# MCU.net
KiCad netlist of a schematic drawn in EAGLE
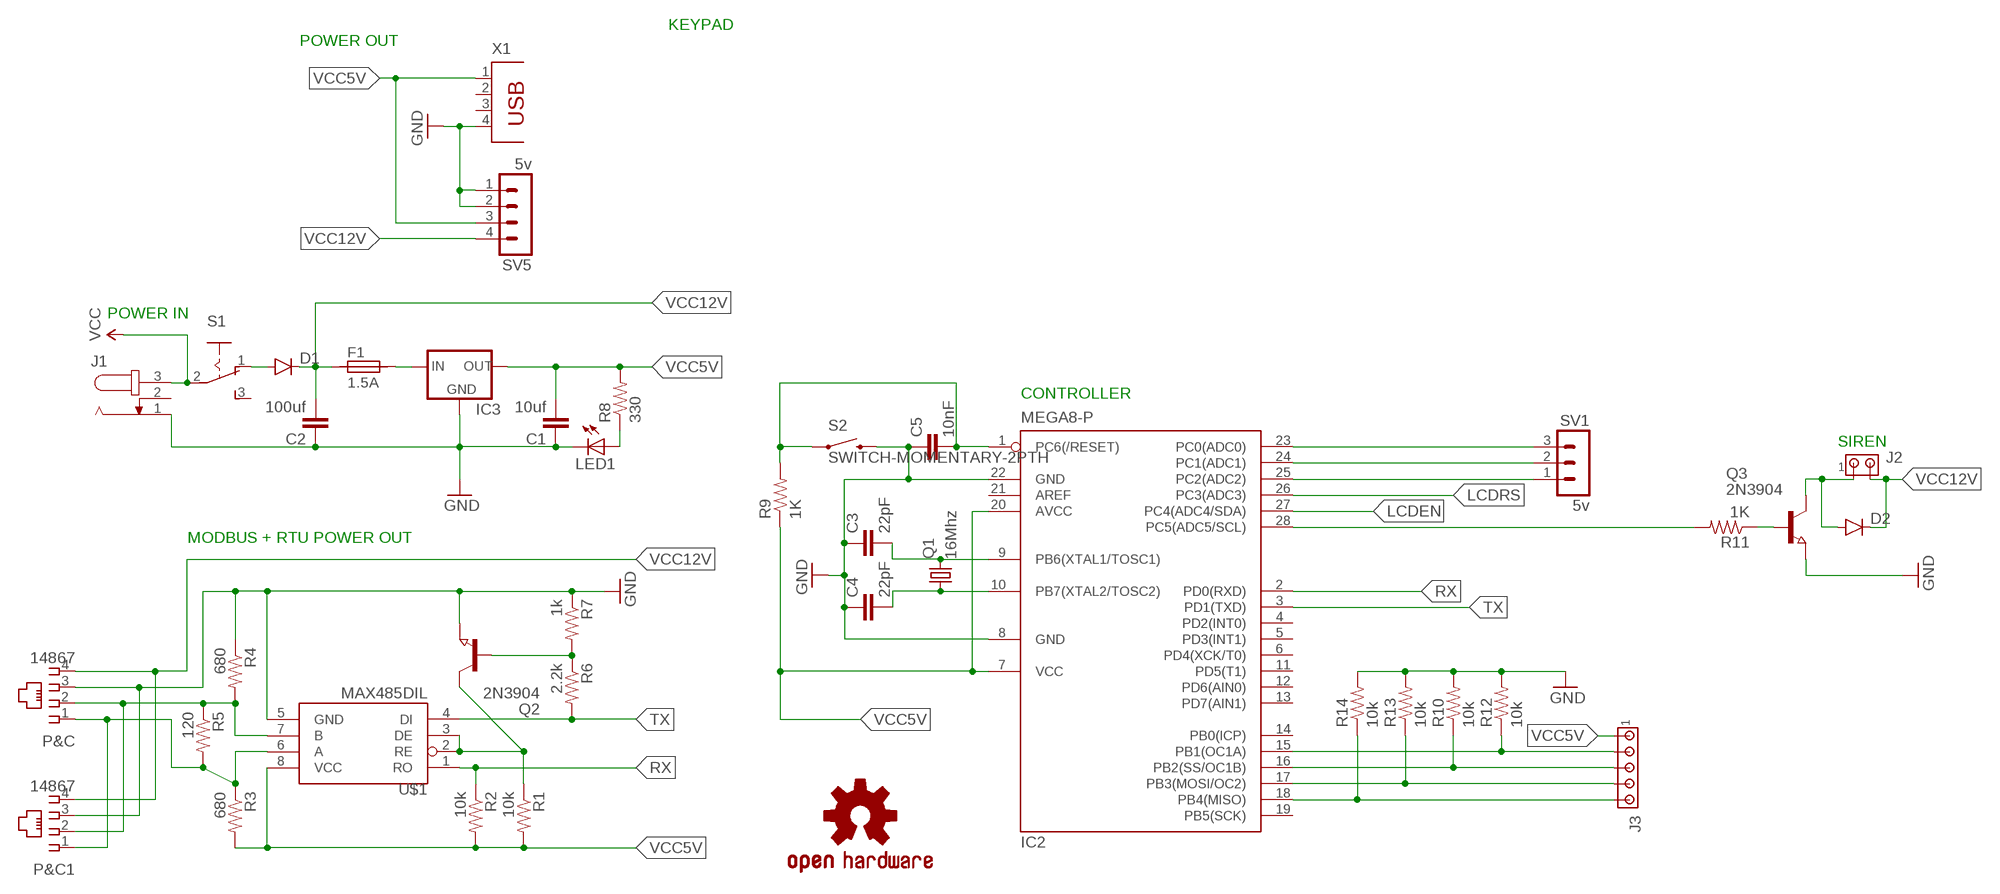
[diagram p0: schematic, sheet 1]

(export (version "E")
  (design (tool "Eeschema 10.0.6"))
  (components
    (comp (ref "C1")
      (value "10uf")
      (footprint "eagle-import:0805")
      (libsource (lib "eagle-import") (part "CAP0805"))
    )
    (comp (ref "C2")
      (value "100uf")
      (footprint "eagle-import:0805")
      (libsource (lib "eagle-import") (part "CAP0805"))
    )
    (comp (ref "C3")
      (value "22pF")
      (footprint "eagle-import:0805")
      (libsource (lib "eagle-import") (part "CAP0805"))
    )
    (comp (ref "C4")
      (value "22pF")
      (footprint "eagle-import:0805")
      (libsource (lib "eagle-import") (part "CAP0805"))
    )
    (comp (ref "C5")
      (value "10nF")
      (footprint "eagle-import:0805")
      (libsource (lib "eagle-import") (part "CAP0805"))
    )
    (comp (ref "D1")
      (value "DIODESMA")
      (footprint "eagle-import:SMA-DIODE")
      (libsource (lib "eagle-import") (part "DIODESMA"))
    )
    (comp (ref "D2")
      (value "DIODESMA")
      (footprint "eagle-import:SMA-DIODE")
      (libsource (lib "eagle-import") (part "DIODESMA"))
    )
    (comp (ref "F1")
      (value "1.5A")
      (footprint "eagle-import:1820")
      (libsource (lib "eagle-import") (part "SIBA194600"))
    )
    (comp (ref "IC2")
      (value "MEGA8-P")
      (footprint "eagle-import:DIL28-3")
      (libsource (lib "eagle-import") (part "MEGA8-P"))
    )
    (comp (ref "IC3")
      (value "V_REG_78XX-TO-220")
      (footprint "eagle-import:TO-220-ALT")
      (libsource (lib "eagle-import") (part "V_REG_78XX-TO-220"))
    )
    (comp (ref "J1")
      (value "JACK-PLUG1")
      (footprint "eagle-import:SPC4078")
      (libsource (lib "eagle-import") (part "JACK-PLUG1"))
    )
    (comp (ref "J2")
      (value "MTA02-156")
      (footprint "eagle-import:1X2MTA")
      (libsource (lib "eagle-import") (part "MTA02-156"))
    )
    (comp (ref "J3")
      (value "MTA05-156")
      (footprint "eagle-import:1X5MTA")
      (libsource (lib "eagle-import") (part "MTA05-156"))
    )
    (comp (ref "LED1")
      (value "LEDCHIP-LED0805")
      (footprint "eagle-import:CHIP-LED0805")
      (libsource (lib "eagle-import") (part "LEDCHIP-LED0805"))
    )
    (comp (ref "LOGO1")
      (value "OSHW-LOGOL")
      (footprint "eagle-import:OSHW-LOGO-L")
      (libsource (lib "eagle-import") (part "OSHW-LOGOL"))
    )
    (comp (ref "P&C")
      (value "14867")
      (footprint "eagle-import:14867")
      (libsource (lib "eagle-import") (part "14867"))
    )
    (comp (ref "P&C1")
      (value "14867")
      (footprint "eagle-import:14867")
      (libsource (lib "eagle-import") (part "14867"))
    )
    (comp (ref "Q1")
      (value "16Mhz")
      (footprint "eagle-import:SM49")
      (libsource (lib "eagle-import") (part "CRYSTALSM49"))
    )
    (comp (ref "Q2")
      (value "2N3904")
      (footprint "eagle-import:SOT23")
      (libsource (lib "eagle-import") (part "NPN-TRANSISTOR_SOT23"))
    )
    (comp (ref "Q3")
      (value "2N3904")
      (footprint "eagle-import:SOT23")
      (libsource (lib "eagle-import") (part "NPN-TRANSISTOR_SOT23"))
    )
    (comp (ref "R1")
      (value "10k")
      (footprint "eagle-import:0805")
      (libsource (lib "eagle-import") (part "RESISTOR0805-RES"))
    )
    (comp (ref "R2")
      (value "10k")
      (footprint "eagle-import:0805")
      (libsource (lib "eagle-import") (part "RESISTOR0805-RES"))
    )
    (comp (ref "R3")
      (value "680")
      (footprint "eagle-import:0805")
      (libsource (lib "eagle-import") (part "RESISTOR0805-RES"))
    )
    (comp (ref "R4")
      (value "680")
      (footprint "eagle-import:0805")
      (libsource (lib "eagle-import") (part "RESISTOR0805-RES"))
    )
    (comp (ref "R5")
      (value "120")
      (footprint "eagle-import:0805")
      (libsource (lib "eagle-import") (part "RESISTOR0805-RES"))
    )
    (comp (ref "R6")
      (value "2.2k")
      (footprint "eagle-import:0805")
      (libsource (lib "eagle-import") (part "RESISTOR0805-RES"))
    )
    (comp (ref "R7")
      (value "1k")
      (footprint "eagle-import:0805")
      (libsource (lib "eagle-import") (part "RESISTOR0805-RES"))
    )
    (comp (ref "R8")
      (value "330")
      (footprint "eagle-import:0805")
      (libsource (lib "eagle-import") (part "RESISTOR0805-RES"))
    )
    (comp (ref "R9")
      (value "1K")
      (footprint "eagle-import:0805")
      (libsource (lib "eagle-import") (part "RESISTOR0805-RES"))
    )
    (comp (ref "R10")
      (value "10k")
      (footprint "eagle-import:0805")
      (libsource (lib "eagle-import") (part "RESISTOR0805-RES"))
    )
    (comp (ref "R11")
      (value "1K")
      (footprint "eagle-import:0805")
      (libsource (lib "eagle-import") (part "RESISTOR0805-RES"))
    )
    (comp (ref "R12")
      (value "10k")
      (footprint "eagle-import:0805")
      (libsource (lib "eagle-import") (part "RESISTOR0805-RES"))
    )
    (comp (ref "R13")
      (value "10k")
      (footprint "eagle-import:0805")
      (libsource (lib "eagle-import") (part "RESISTOR0805-RES"))
    )
    (comp (ref "R14")
      (value "10k")
      (footprint "eagle-import:0805")
      (libsource (lib "eagle-import") (part "RESISTOR0805-RES"))
    )
    (comp (ref "S1")
      (value "255SB")
      (footprint "eagle-import:255SB")
      (libsource (lib "eagle-import") (part "255SB"))
    )
    (comp (ref "S2")
      (value "SWITCH-MOMENTARY-2PTH")
      (footprint "eagle-import:TACTILE-PTH")
      (libsource (lib "eagle-import") (part "SWITCH-MOMENTARY-2PTH"))
    )
    (comp (ref "SV1")
      (value "5v")
      (footprint "eagle-import:MA03-1")
      (libsource (lib "eagle-import") (part "MA03-1"))
    )
    (comp (ref "SV5")
      (value "5v")
      (footprint "eagle-import:MA04-1")
      (libsource (lib "eagle-import") (part "MA04-1"))
    )
    (comp (ref "U$1")
      (value "MAX485DIL")
      (footprint "eagle-import:DIL08")
      (libsource (lib "eagle-import") (part "MAX485DIL"))
    )
    (comp (ref "X1")
      (value "PN87520")
      (footprint "eagle-import:PN87520")
      (libsource (lib "eagle-import") (part "PN87520"))
    )
  )
  (nets
    (net (code "1") (name "GND") (class "Default")
      (node (ref "C1") (pin "1") (pinfunction "1_1") (pintype "passive"))
      (node (ref "C2") (pin "1") (pinfunction "1_1") (pintype "passive"))
      (node (ref "C3") (pin "1") (pinfunction "1_1") (pintype "passive"))
      (node (ref "C4") (pin "1") (pinfunction "1_1") (pintype "passive"))
      (node (ref "C5") (pin "1") (pinfunction "1_1") (pintype "passive"))
      (node (ref "IC2") (pin "22") (pinfunction "GND_22") (pintype "power_in"))
      (node (ref "IC2") (pin "8") (pinfunction "GND_8") (pintype "power_in"))
      (node (ref "IC3") (pin "GND") (pinfunction "GND_GND") (pintype "input"))
      (node (ref "J1") (pin "1") (pinfunction "1_1") (pintype "passive"))
      (node (ref "LED1") (pin "C") (pinfunction "C_C") (pintype "passive"))
      (node (ref "P&C") (pin "3") (pinfunction "3_3") (pintype "passive"))
      (node (ref "P&C1") (pin "3") (pinfunction "3_3") (pintype "passive"))
      (node (ref "Q2") (pin "2") (pinfunction "E_2") (pintype "passive"))
      (node (ref "Q3") (pin "2") (pinfunction "E_2") (pintype "passive"))
      (node (ref "R10") (pin "2") (pinfunction "2_2") (pintype "passive"))
      (node (ref "R12") (pin "2") (pinfunction "2_2") (pintype "passive"))
      (node (ref "R13") (pin "2") (pinfunction "2_2") (pintype "passive"))
      (node (ref "R14") (pin "2") (pinfunction "2_2") (pintype "passive"))
      (node (ref "R4") (pin "1") (pinfunction "1_1") (pintype "passive"))
      (node (ref "R7") (pin "1") (pinfunction "1_1") (pintype "passive"))
      (node (ref "S2") (pin "3") (pinfunction "2_3") (pintype "passive"))
      (node (ref "SV5") (pin "1") (pinfunction "1_1") (pintype "passive"))
      (node (ref "SV5") (pin "2") (pinfunction "2_2") (pintype "passive"))
      (node (ref "U$1") (pin "5") (pinfunction "GND_5") (pintype "bidirectional"))
      (node (ref "X1") (pin "4") (pinfunction "4_4") (pintype "passive"))
    )
    (net (code "2") (name "LCDEN") (class "Default")
      (node (ref "IC2") (pin "27") (pinfunction "PC4(ADC4/SDA)_27") (pintype "bidirectional"))
    )
    (net (code "3") (name "LCDRS") (class "Default")
      (node (ref "IC2") (pin "26") (pinfunction "PC3(ADC3)_26") (pintype "bidirectional"))
    )
    (net (code "4") (name "Net-(F1-Pad2)") (class "Default")
      (node (ref "F1") (pin "2") (pinfunction "2_2") (pintype "passive"))
      (node (ref "IC3") (pin "IN") (pinfunction "IN_IN") (pintype "input"))
    )
    (net (code "5") (name "Net-(IC2-PB1(OC1A))") (class "Default")
      (node (ref "IC2") (pin "15") (pinfunction "PB1(OC1A)_15") (pintype "bidirectional"))
      (node (ref "J3") (pin "2") (pinfunction "2_2") (pintype "passive"))
      (node (ref "R12") (pin "1") (pinfunction "1_1") (pintype "passive"))
    )
    (net (code "6") (name "Net-(IC2-PB2(SS{slash}OC1B))") (class "Default")
      (node (ref "IC2") (pin "16") (pinfunction "PB2(SS/OC1B)_16") (pintype "bidirectional"))
      (node (ref "J3") (pin "3") (pinfunction "3_3") (pintype "passive"))
      (node (ref "R10") (pin "1") (pinfunction "1_1") (pintype "passive"))
    )
    (net (code "7") (name "Net-(IC2-PB3(MOSI{slash}OC2))") (class "Default")
      (node (ref "IC2") (pin "17") (pinfunction "PB3(MOSI/OC2)_17") (pintype "bidirectional"))
      (node (ref "J3") (pin "4") (pinfunction "4_4") (pintype "passive"))
      (node (ref "R13") (pin "1") (pinfunction "1_1") (pintype "passive"))
    )
    (net (code "8") (name "Net-(IC2-PB4(MISO))") (class "Default")
      (node (ref "IC2") (pin "18") (pinfunction "PB4(MISO)_18") (pintype "bidirectional"))
      (node (ref "J3") (pin "5") (pinfunction "5_5") (pintype "passive"))
      (node (ref "R14") (pin "1") (pinfunction "1_1") (pintype "passive"))
    )
    (net (code "9") (name "Net-(IC2-PB6(XTAL1{slash}TOSC1))") (class "Default")
      (node (ref "C3") (pin "2") (pinfunction "2_2") (pintype "passive"))
      (node (ref "IC2") (pin "9") (pinfunction "PB6(XTAL1/TOSC1)_9") (pintype "bidirectional"))
      (node (ref "Q1") (pin "2") (pinfunction "2_2") (pintype "passive"))
    )
    (net (code "10") (name "Net-(IC2-PB7(XTAL2{slash}TOSC2))") (class "Default")
      (node (ref "C4") (pin "2") (pinfunction "2_2") (pintype "passive"))
      (node (ref "IC2") (pin "10") (pinfunction "PB7(XTAL2/TOSC2)_10") (pintype "bidirectional"))
      (node (ref "Q1") (pin "1") (pinfunction "1_1") (pintype "passive"))
    )
    (net (code "11") (name "Net-(IC2-PC0(ADC0))") (class "Default")
      (node (ref "IC2") (pin "23") (pinfunction "PC0(ADC0)_23") (pintype "bidirectional"))
      (node (ref "SV1") (pin "3") (pinfunction "3_3") (pintype "passive"))
    )
    (net (code "12") (name "Net-(IC2-PC1(ADC1))") (class "Default")
      (node (ref "IC2") (pin "24") (pinfunction "PC1(ADC1)_24") (pintype "bidirectional"))
      (node (ref "SV1") (pin "2") (pinfunction "2_2") (pintype "passive"))
    )
    (net (code "13") (name "Net-(IC2-PC2(ADC2))") (class "Default")
      (node (ref "IC2") (pin "25") (pinfunction "PC2(ADC2)_25") (pintype "bidirectional"))
      (node (ref "SV1") (pin "1") (pinfunction "1_1") (pintype "passive"))
    )
    (net (code "14") (name "Net-(IC2-PC5(ADC5{slash}SCL))") (class "Default")
      (node (ref "IC2") (pin "28") (pinfunction "PC5(ADC5/SCL)_28") (pintype "bidirectional"))
      (node (ref "R11") (pin "2") (pinfunction "2_2") (pintype "passive"))
    )
    (net (code "15") (name "Net-(IC2-PC6({slash}RESET))") (class "Default")
      (node (ref "C5") (pin "2") (pinfunction "2_2") (pintype "passive"))
      (node (ref "IC2") (pin "1") (pinfunction "PC6(/RESET)_1") (pintype "bidirectional"))
      (node (ref "R9") (pin "2") (pinfunction "2_2") (pintype "passive"))
      (node (ref "S2") (pin "1") (pinfunction "1_1") (pintype "passive"))
    )
    (net (code "16") (name "Net-(LED1-PadA)") (class "Default")
      (node (ref "LED1") (pin "A") (pinfunction "A_A") (pintype "passive"))
      (node (ref "R8") (pin "1") (pinfunction "1_1") (pintype "passive"))
    )
    (net (code "17") (name "Net-(Q2-B)") (class "Default")
      (node (ref "Q2") (pin "1") (pinfunction "B_1") (pintype "passive"))
      (node (ref "R6") (pin "1") (pinfunction "1_1") (pintype "passive"))
      (node (ref "R7") (pin "2") (pinfunction "2_2") (pintype "passive"))
    )
    (net (code "18") (name "Net-(Q2-C)") (class "Default")
      (node (ref "Q2") (pin "3") (pinfunction "C_3") (pintype "passive"))
      (node (ref "R1") (pin "1") (pinfunction "1_1") (pintype "passive"))
      (node (ref "U$1") (pin "2") (pinfunction "RE_2") (pintype "bidirectional"))
      (node (ref "U$1") (pin "3") (pinfunction "DE_3") (pintype "bidirectional"))
    )
    (net (code "19") (name "Net-(Q3-B)") (class "Default")
      (node (ref "Q3") (pin "1") (pinfunction "B_1") (pintype "passive"))
      (node (ref "R11") (pin "1") (pinfunction "1_1") (pintype "passive"))
    )
    (net (code "20") (name "Net-(Q3-C)") (class "Default")
      (node (ref "D2") (pin "A") (pinfunction "A_A") (pintype "passive"))
      (node (ref "J2") (pin "1") (pinfunction "1_1") (pintype "passive"))
      (node (ref "Q3") (pin "3") (pinfunction "C_3") (pintype "passive"))
    )
    (net (code "21") (name "Net-(S1-O)") (class "Default")
      (node (ref "D1") (pin "A") (pinfunction "A_A") (pintype "passive"))
      (node (ref "S1") (pin "1") (pinfunction "O_1") (pintype "passive"))
    )
    (net (code "22") (name "Net-(U$1-A)") (class "Default")
      (node (ref "P&C") (pin "1") (pinfunction "1_1") (pintype "passive"))
      (node (ref "P&C1") (pin "1") (pinfunction "1_1") (pintype "passive"))
      (node (ref "R3") (pin "1") (pinfunction "1_1") (pintype "passive"))
      (node (ref "R5") (pin "2") (pinfunction "2_2") (pintype "passive"))
      (node (ref "U$1") (pin "6") (pinfunction "A_6") (pintype "bidirectional"))
    )
    (net (code "23") (name "Net-(U$1-B)") (class "Default")
      (node (ref "P&C") (pin "2") (pinfunction "2_2") (pintype "passive"))
      (node (ref "P&C1") (pin "2") (pinfunction "2_2") (pintype "passive"))
      (node (ref "R4") (pin "2") (pinfunction "2_2") (pintype "passive"))
      (node (ref "R5") (pin "1") (pinfunction "1_1") (pintype "passive"))
      (node (ref "U$1") (pin "7") (pinfunction "B_7") (pintype "bidirectional"))
    )
    (net (code "24") (name "RX") (class "Default")
      (node (ref "IC2") (pin "2") (pinfunction "PD0(RXD)_2") (pintype "bidirectional"))
      (node (ref "R2") (pin "1") (pinfunction "1_1") (pintype "passive"))
      (node (ref "U$1") (pin "1") (pinfunction "RO_1") (pintype "bidirectional"))
    )
    (net (code "25") (name "TX") (class "Default")
      (node (ref "IC2") (pin "3") (pinfunction "PD1(TXD)_3") (pintype "bidirectional"))
      (node (ref "R6") (pin "2") (pinfunction "2_2") (pintype "passive"))
      (node (ref "U$1") (pin "4") (pinfunction "DI_4") (pintype "bidirectional"))
    )
    (net (code "26") (name "VCC") (class "Default")
      (node (ref "J1") (pin "3") (pinfunction "3_3") (pintype "passive"))
      (node (ref "S1") (pin "2") (pinfunction "P_2") (pintype "passive"))
    )
    (net (code "27") (name "VCC5V") (class "Default")
      (node (ref "C1") (pin "2") (pinfunction "2_2") (pintype "passive"))
      (node (ref "IC2") (pin "20") (pinfunction "AVCC_20") (pintype "power_in"))
      (node (ref "IC2") (pin "7") (pinfunction "VCC_7") (pintype "power_in"))
      (node (ref "IC3") (pin "OUT") (pinfunction "OUT_OUT") (pintype "output"))
      (node (ref "J3") (pin "1") (pinfunction "1_1") (pintype "passive"))
      (node (ref "R1") (pin "2") (pinfunction "2_2") (pintype "passive"))
      (node (ref "R2") (pin "2") (pinfunction "2_2") (pintype "passive"))
      (node (ref "R3") (pin "2") (pinfunction "2_2") (pintype "passive"))
      (node (ref "R8") (pin "2") (pinfunction "2_2") (pintype "passive"))
      (node (ref "R9") (pin "1") (pinfunction "1_1") (pintype "passive"))
      (node (ref "SV5") (pin "3") (pinfunction "3_3") (pintype "passive"))
      (node (ref "U$1") (pin "8") (pinfunction "VCC_8") (pintype "bidirectional"))
      (node (ref "X1") (pin "1") (pinfunction "1_1") (pintype "passive"))
    )
    (net (code "28") (name "VCC12V") (class "Default")
      (node (ref "C2") (pin "2") (pinfunction "2_2") (pintype "passive"))
      (node (ref "D1") (pin "C") (pinfunction "C_C") (pintype "passive"))
      (node (ref "D2") (pin "C") (pinfunction "C_C") (pintype "passive"))
      (node (ref "F1") (pin "1") (pinfunction "1_1") (pintype "passive"))
      (node (ref "J2") (pin "2") (pinfunction "2_2") (pintype "passive"))
      (node (ref "P&C") (pin "4") (pinfunction "4_4") (pintype "passive"))
      (node (ref "P&C1") (pin "4") (pinfunction "4_4") (pintype "passive"))
      (node (ref "SV5") (pin "4") (pinfunction "4_4") (pintype "passive"))
    )
    (net (code "29") (name "unconnected-(IC2-AREF-Pad21)") (class "Default")
      (node (ref "IC2") (pin "21") (pinfunction "AREF_21") (pintype "passive"))
    )
    (net (code "30") (name "unconnected-(IC2-PB0(ICP)-Pad14)") (class "Default")
      (node (ref "IC2") (pin "14") (pinfunction "PB0(ICP)_14") (pintype "bidirectional"))
    )
    (net (code "31") (name "unconnected-(IC2-PB5(SCK)-Pad19)") (class "Default")
      (node (ref "IC2") (pin "19") (pinfunction "PB5(SCK)_19") (pintype "bidirectional"))
    )
    (net (code "32") (name "unconnected-(IC2-PD2(INT0)-Pad4)") (class "Default")
      (node (ref "IC2") (pin "4") (pinfunction "PD2(INT0)_4") (pintype "bidirectional"))
    )
    (net (code "33") (name "unconnected-(IC2-PD3(INT1)-Pad5)") (class "Default")
      (node (ref "IC2") (pin "5") (pinfunction "PD3(INT1)_5") (pintype "bidirectional"))
    )
    (net (code "34") (name "unconnected-(IC2-PD4(XCK{slash}T0)-Pad6)") (class "Default")
      (node (ref "IC2") (pin "6") (pinfunction "PD4(XCK/T0)_6") (pintype "bidirectional"))
    )
    (net (code "35") (name "unconnected-(IC2-PD5(T1)-Pad11)") (class "Default")
      (node (ref "IC2") (pin "11") (pinfunction "PD5(T1)_11") (pintype "bidirectional"))
    )
    (net (code "36") (name "unconnected-(IC2-PD6(AIN0)-Pad12)") (class "Default")
      (node (ref "IC2") (pin "12") (pinfunction "PD6(AIN0)_12") (pintype "bidirectional"))
    )
    (net (code "37") (name "unconnected-(IC2-PD7(AIN1)-Pad13)") (class "Default")
      (node (ref "IC2") (pin "13") (pinfunction "PD7(AIN1)_13") (pintype "bidirectional"))
    )
    (net (code "38") (name "unconnected-(J1-Pad2)") (class "Default")
      (node (ref "J1") (pin "2") (pinfunction "2_2") (pintype "passive"))
    )
    (net (code "39") (name "unconnected-(S1-S-Pad3)") (class "Default")
      (node (ref "S1") (pin "3") (pinfunction "S_3") (pintype "passive"))
    )
    (net (code "40") (name "unconnected-(X1-Pad2)") (class "Default")
      (node (ref "X1") (pin "2") (pinfunction "2_2") (pintype "passive"))
    )
    (net (code "41") (name "unconnected-(X1-Pad3)") (class "Default")
      (node (ref "X1") (pin "3") (pinfunction "3_3") (pintype "passive"))
    )
  )
)
